# Audio.net
KiCad netlist of a schematic drawn in Altium Designer
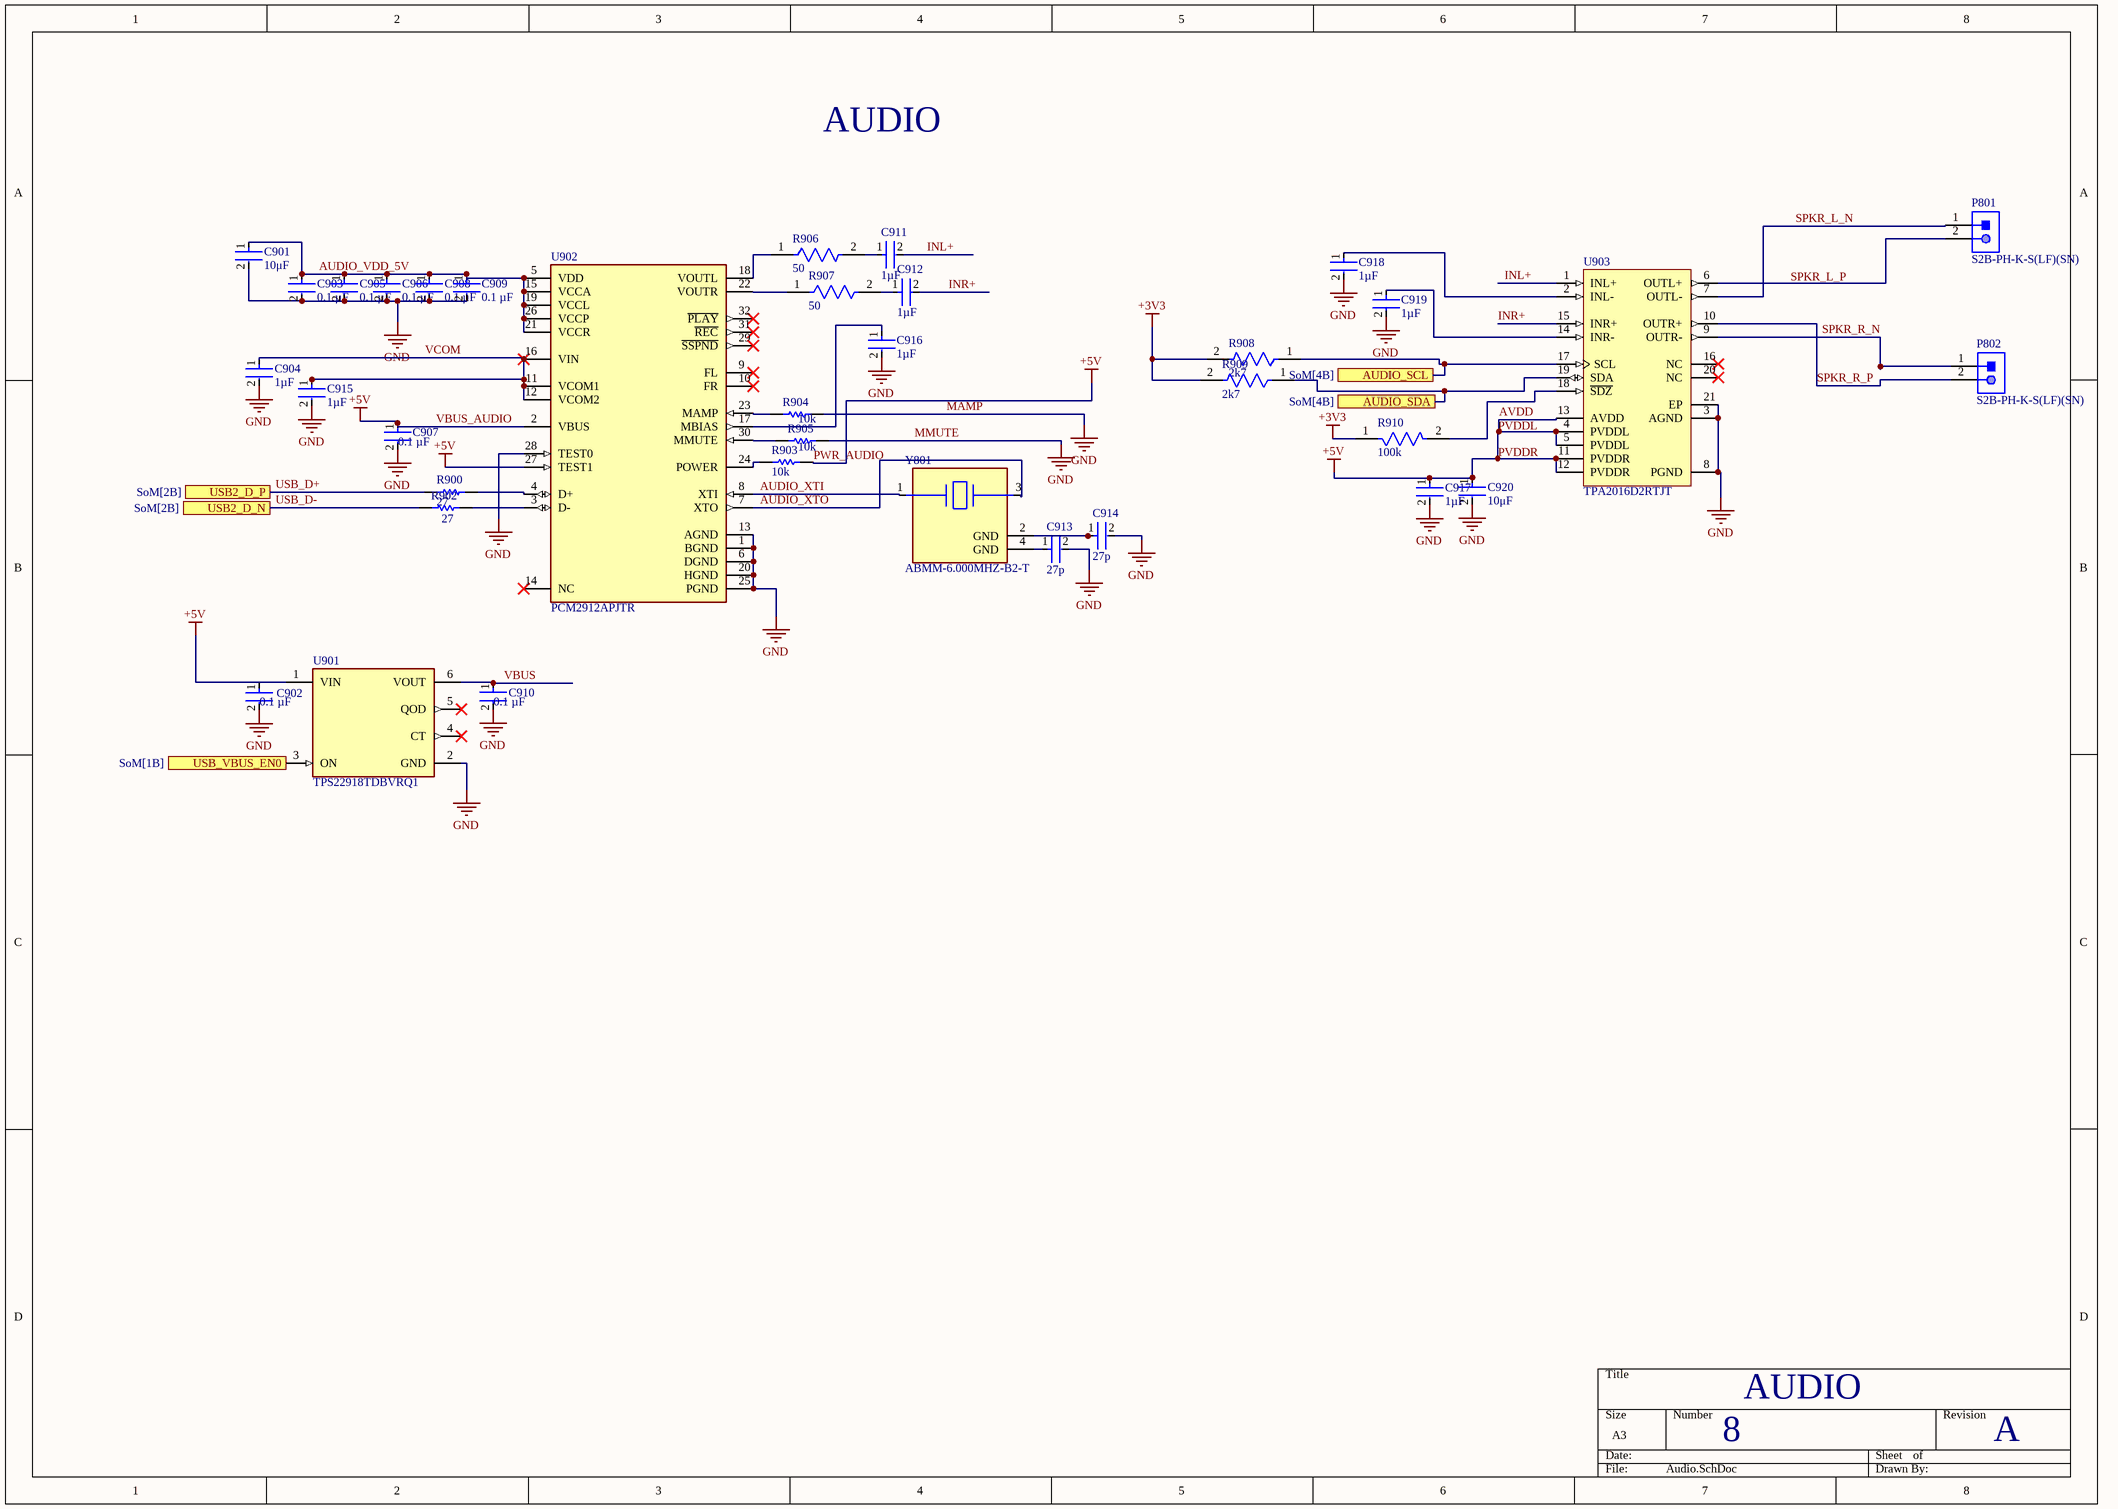
[diagram p0: Audio.SchDoc]

(export (version "E")
  (design (tool "Eeschema 10.0.6"))
  (components
    (comp (ref "C901")
      (value "10μF")
      (footprint "FP-GRM31C-0_2-e0_3_0_8-MFG")
      (description "Chip Multilayer Ceramic Capacitors for General Purpose, 1206, 10uF, X7R, 15%, 10%, 25V")
      (fields (field (name "TOLERANCE") "10%") (field (name "VOLTAGE") "25V"))
      (libsource (lib "Altium Content Vault") (part "02cd4be3c70576c341d710602a673aa"))
    )
    (comp (ref "C902")
      (value "0.1 µF")
      (footprint "FP-GRM155-0_05-IPC_B")
      (description "Chip Multilayer Ceramic Capacitors for General Purpose, 0402, 0.10uF, X7R, 15%, 10%, 50V")
      (fields (field (name "TOLERANCE") "10%"))
      (libsource (lib "Altium Content Vault") (part "02cd4be3c70576c341d710602a673aa"))
    )
    (comp (ref "C903")
      (value "0.1 µF")
      (footprint "FP-GRM155-0_05-IPC_B")
      (description "Chip Multilayer Ceramic Capacitors for General Purpose, 0402, 0.10uF, X7R, 15%, 10%, 50V")
      (fields (field (name "TOLERANCE") "10%"))
      (libsource (lib "Altium Content Vault") (part "02cd4be3c70576c341d710602a673aa"))
    )
    (comp (ref "C904")
      (value "1µF")
      (footprint "FP-GRM15-0_1-MFG")
      (description "CAP CER 1UF 10V X5R 0402")
      (fields
        (field (name "OCTOPART") "https://octopart.com/grm155r61a105ke15d-murata-197442")
        (field (name "MANUFACTURER PART NUMBER") "GRM155R61A105KE15D")
      )
      (libsource (lib "Altium Content Vault") (part "02cd4be3c70576c341d710602a673aa"))
    )
    (comp (ref "C905")
      (value "0.1 µF")
      (footprint "FP-GRM155-0_05-IPC_B")
      (description "Chip Multilayer Ceramic Capacitors for General Purpose, 0402, 0.10uF, X7R, 15%, 10%, 50V")
      (fields (field (name "TOLERANCE") "10%"))
      (libsource (lib "Altium Content Vault") (part "02cd4be3c70576c341d710602a673aa"))
    )
    (comp (ref "C906")
      (value "0.1 µF")
      (footprint "FP-GRM155-0_05-IPC_B")
      (description "Chip Multilayer Ceramic Capacitors for General Purpose, 0402, 0.10uF, X7R, 15%, 10%, 50V")
      (fields (field (name "TOLERANCE") "10%"))
      (libsource (lib "Altium Content Vault") (part "02cd4be3c70576c341d710602a673aa"))
    )
    (comp (ref "C907")
      (value "0.1 µF")
      (footprint "FP-GRM155-0_05-IPC_B")
      (description "Chip Multilayer Ceramic Capacitors for General Purpose, 0402, 0.10uF, X7R, 15%, 10%, 50V")
      (fields (field (name "TOLERANCE") "10%"))
      (libsource (lib "Altium Content Vault") (part "02cd4be3c70576c341d710602a673aa"))
    )
    (comp (ref "C908")
      (value "0.1 µF")
      (footprint "FP-GRM155-0_05-IPC_B")
      (description "Chip Multilayer Ceramic Capacitors for General Purpose, 0402, 0.10uF, X7R, 15%, 10%, 50V")
      (fields (field (name "TOLERANCE") "10%"))
      (libsource (lib "Altium Content Vault") (part "02cd4be3c70576c341d710602a673aa"))
    )
    (comp (ref "C909")
      (value "0.1 µF")
      (footprint "FP-GRM155-0_05-IPC_B")
      (description "Chip Multilayer Ceramic Capacitors for General Purpose, 0402, 0.10uF, X7R, 15%, 10%, 50V")
      (fields (field (name "TOLERANCE") "10%"))
      (libsource (lib "Altium Content Vault") (part "02cd4be3c70576c341d710602a673aa"))
    )
    (comp (ref "C910")
      (value "0.1 µF")
      (footprint "FP-GRM155-0_05-IPC_B")
      (description "Chip Multilayer Ceramic Capacitors for General Purpose, 0402, 0.10uF, X7R, 15%, 10%, 50V")
      (fields (field (name "TOLERANCE") "10%"))
      (libsource (lib "Altium Content Vault") (part "02cd4be3c70576c341d710602a673aa"))
    )
    (comp (ref "C911")
      (value "1µF")
      (footprint "FP-GRM15-0_1-MFG")
      (description "CAP CER 1UF 10V X5R 0402")
      (fields
        (field (name "OCTOPART") "https://octopart.com/grm155r61a105ke15d-murata-197442")
        (field (name "MANUFACTURER PART NUMBER") "GRM155R61A105KE15D")
      )
      (libsource (lib "Altium Content Vault") (part "02cd4be3c70576c341d710602a673aa"))
    )
    (comp (ref "C912")
      (value "1µF")
      (footprint "FP-GRM15-0_1-MFG")
      (description "CAP CER 1UF 10V X5R 0402")
      (fields
        (field (name "OCTOPART") "https://octopart.com/grm155r61a105ke15d-murata-197442")
        (field (name "MANUFACTURER PART NUMBER") "GRM155R61A105KE15D")
      )
      (libsource (lib "Altium Content Vault") (part "02cd4be3c70576c341d710602a673aa"))
    )
    (comp (ref "C913")
      (value "27p")
      (footprint "FP-C0603C-CF-MFG")
      (description "C0603 27 pF X7R 30ppm/°C 5.00% 50 V")
      (fields
        (field (name "OCTOPART") "https://octopart.com/c0603c270j5ractu-kemet-82267354")
        (field (name "TOLERANCE") "0.05")
      )
      (libsource (lib "Altium Content Vault") (part "b4654b650e69147ec39a6b967a45e02"))
    )
    (comp (ref "C914")
      (value "27p")
      (footprint "FP-C0603C-CF-MFG")
      (description "C0603 27 pF X7R 30ppm/°C 5.00% 50 V")
      (fields
        (field (name "OCTOPART") "https://octopart.com/c0603c270j5ractu-kemet-82267354")
        (field (name "TOLERANCE") "0.05")
      )
      (libsource (lib "Altium Content Vault") (part "b4654b650e69147ec39a6b967a45e02"))
    )
    (comp (ref "C915")
      (value "1µF")
      (footprint "FP-GRM15-0_1-MFG")
      (description "CAP CER 1UF 10V X5R 0402")
      (fields
        (field (name "OCTOPART") "https://octopart.com/grm155r61a105ke15d-murata-197442")
        (field (name "MANUFACTURER PART NUMBER") "GRM155R61A105KE15D")
      )
      (libsource (lib "Altium Content Vault") (part "02cd4be3c70576c341d710602a673aa"))
    )
    (comp (ref "C916")
      (value "1µF")
      (footprint "FP-GRM15-0_1-MFG")
      (description "CAP CER 1UF 10V X5R 0402")
      (fields
        (field (name "OCTOPART") "https://octopart.com/grm155r61a105ke15d-murata-197442")
        (field (name "MANUFACTURER PART NUMBER") "GRM155R61A105KE15D")
      )
      (libsource (lib "Altium Content Vault") (part "02cd4be3c70576c341d710602a673aa"))
    )
    (comp (ref "C917")
      (value "1µF")
      (footprint "FP-GRM15-0_1-MFG")
      (description "CAP CER 1UF 10V X5R 0402")
      (fields
        (field (name "OCTOPART") "https://octopart.com/grm155r61a105ke15d-murata-197442")
        (field (name "MANUFACTURER PART NUMBER") "GRM155R61A105KE15D")
      )
      (libsource (lib "Altium Content Vault") (part "02cd4be3c70576c341d710602a673aa"))
    )
    (comp (ref "C918")
      (value "1µF")
      (footprint "FP-GRM15-0_1-MFG")
      (description "CAP CER 1UF 10V X5R 0402")
      (fields
        (field (name "OCTOPART") "https://octopart.com/grm155r61a105ke15d-murata-197442")
        (field (name "MANUFACTURER PART NUMBER") "GRM155R61A105KE15D")
      )
      (libsource (lib "Altium Content Vault") (part "02cd4be3c70576c341d710602a673aa"))
    )
    (comp (ref "C919")
      (value "1µF")
      (footprint "FP-GRM15-0_1-MFG")
      (description "CAP CER 1UF 10V X5R 0402")
      (fields
        (field (name "OCTOPART") "https://octopart.com/grm155r61a105ke15d-murata-197442")
        (field (name "MANUFACTURER PART NUMBER") "GRM155R61A105KE15D")
      )
      (libsource (lib "Altium Content Vault") (part "02cd4be3c70576c341d710602a673aa"))
    )
    (comp (ref "C920")
      (value "10μF")
      (footprint "FP-GRM31C-0_2-e0_3_0_8-MFG")
      (description "Chip Multilayer Ceramic Capacitors for General Purpose, 1206, 10uF, X7R, 15%, 10%, 25V")
      (fields (field (name "TOLERANCE") "10%") (field (name "VOLTAGE") "25V"))
      (libsource (lib "Altium Content Vault") (part "02cd4be3c70576c341d710602a673aa"))
    )
    (comp (ref "P801")
      (value "S2B-PH-K-S(LF)(SN)")
      (footprint "JST-S2B-PH-K-S_V")
      (fields (field (name "TOLERANCE") "20%"))
      (libsource (lib "Altium Content Vault") (part "CN-1P-M-R2"))
    )
    (comp (ref "P802")
      (value "S2B-PH-K-S(LF)(SN)")
      (footprint "JST-S2B-PH-K-S_V")
      (fields (field (name "TOLERANCE") "20%"))
      (libsource (lib "Altium Content Vault") (part "CN-1P-M-R2"))
    )
    (comp (ref "R900")
      (value "27")
      (footprint "RESC1005X40X25LL05T10")
      (fields (field (name "PART NUMBER") "RC0402FR-0727RL") (field (name "MANUFACTURER") "Yageo / Phycomp"))
      (libsource (lib "Altium Content Vault") (part "RES"))
    )
    (comp (ref "R902")
      (value "27")
      (footprint "RESC1005X40X25LL05T10")
      (fields (field (name "PART NUMBER") "RC0402FR-0727RL") (field (name "MANUFACTURER") "Yageo / Phycomp"))
      (libsource (lib "Altium Content Vault") (part "RES"))
    )
    (comp (ref "R903")
      (value "10k")
      (footprint "RESC1005X40X25LL05T10")
      (fields (field (name "PART NUMBER") "RC0402FR-0710KL") (field (name "MANUFACTURER") "Yageo / Phycomp"))
      (libsource (lib "Altium Content Vault") (part "RES"))
    )
    (comp (ref "R904")
      (value "10k")
      (footprint "RESC1005X40X25LL05T10")
      (fields (field (name "PART NUMBER") "RC0402FR-0710KL") (field (name "MANUFACTURER") "Yageo / Phycomp"))
      (libsource (lib "Altium Content Vault") (part "RES"))
    )
    (comp (ref "R905")
      (value "10k")
      (footprint "RESC1005X40X25LL05T10")
      (fields (field (name "PART NUMBER") "RC0402FR-0710KL") (field (name "MANUFACTURER") "Yageo / Phycomp"))
      (libsource (lib "Altium Content Vault") (part "RES"))
    )
    (comp (ref "R906")
      (value "50")
      (footprint "FP-CRCW0603-e3-MFG")
      (description "RES Thick Film, 50Ω, 1%, 0.1W, 100ppm/°C, 0603")
      (fields (field (name "TOLERANCE") "1%"))
      (libsource (lib "Altium Content Vault") (part "1029c3af85768c4190bb7ad29bc67b5"))
    )
    (comp (ref "R907")
      (value "50")
      (footprint "FP-CRCW0603-e3-MFG")
      (description "RES Thick Film, 50Ω, 1%, 0.1W, 100ppm/°C, 0603")
      (fields (field (name "TOLERANCE") "1%"))
      (libsource (lib "Altium Content Vault") (part "1029c3af85768c4190bb7ad29bc67b5"))
    )
    (comp (ref "R908")
      (value "2k7")
      (footprint "FP-CR0402-IPC_B")
      (description "Thick Film Chip Resistors 0402 2.7kΩ 0.0625W 1% 100ppm/°C")
      (fields (field (name "TOLERANCE") "1%"))
      (libsource (lib "Altium Content Vault") (part "1029c3af85768c4190bb7ad29bc67b5"))
    )
    (comp (ref "R909")
      (value "2k7")
      (footprint "FP-CR0402-IPC_B")
      (description "Thick Film Chip Resistors 0402 2.7kΩ 0.0625W 1% 100ppm/°C")
      (fields (field (name "TOLERANCE") "1%"))
      (libsource (lib "Altium Content Vault") (part "1029c3af85768c4190bb7ad29bc67b5"))
    )
    (comp (ref "R910")
      (value "100k")
      (footprint "FP-RC0402-0_4-IPC_A")
      (description "RES 100K OHM 5% 1/16W 0402")
      (fields (field (name "TOLERANCE") "5%"))
      (libsource (lib "Altium Content Vault") (part "1029c3af85768c4190bb7ad29bc67b5"))
    )
    (comp (ref "U901")
      (value "TPS22918TDBVRQ1")
      (footprint "FP-DBV0006A-IPC_C")
      (description "IC PWR SWITCH N-CHAN 1:1 SOT23-6")
      (libsource (lib "Altium Content Vault") (part "8b1f3cf37ce29d5f7477cf0fde67f53"))
    )
    (comp (ref "U902")
      (value "PCM2912APJTR")
      (footprint "FP-PJT0032A-IPC_C")
      (description "IC STEREO AUD CODEC W/USB 32TQFP")
      (libsource (lib "Altium Content Vault") (part "253ddf6499021ded57be087bdc4fbd2"))
    )
    (comp (ref "U903")
      (value "TPA2016D2RTJT")
      (footprint "RTJ0020D_V")
      (fields (field (name "MANUFACTURER") "Texas Instruments"))
      (libsource (lib "Altium Content Vault") (part "TI-TPA2016D2RTJ20-2700X2700TP"))
    )
    (comp (ref "Y801")
      (value "ABMM-6.000MHZ-B2-T")
      (footprint "FP-ABMM-MFG")
      (description "CRYSTAL 6.0000MHZ 18PF SMD")
      (fields (field (name "TOLERANCE") "20ppm"))
      (libsource (lib "Altium Content Vault") (part "14e648fd3e94df574add110f4c202a0"))
    )
  )
  (nets
    (net (code "1") (name "+3V3") (class "Default")
      (node (ref "R908") (pin "2") (pinfunction "2_2") (pintype "passive"))
      (node (ref "R909") (pin "2") (pinfunction "2_2") (pintype "passive"))
      (node (ref "R910") (pin "1") (pinfunction "1_1") (pintype "passive"))
    )
    (net (code "2") (name "+5V") (class "Default")
      (node (ref "C917") (pin "1") (pinfunction "1_1") (pintype "passive"))
      (node (ref "C920") (pin "1") (pinfunction "1_1") (pintype "passive"))
      (node (ref "R903") (pin "1") (pinfunction "1_1") (pintype "passive"))
      (node (ref "U901") (pin "1") (pinfunction "VIN_1") (pintype "power_in"))
      (node (ref "U902") (pin "27") (pinfunction "TEST1_27") (pintype "input"))
      (node (ref "U903") (pin "11") (pinfunction "PVDDR_11") (pintype "power_in"))
      (node (ref "U903") (pin "12") (pinfunction "PVDDR_12") (pintype "power_in"))
      (node (ref "U903") (pin "13") (pinfunction "AVDD_13") (pintype "power_in"))
      (node (ref "U903") (pin "4") (pinfunction "PVDDL_4") (pintype "power_in"))
      (node (ref "U903") (pin "5") (pinfunction "PVDDL_5") (pintype "power_in"))
    )
    (net (code "3") (name "/AUDIO_SCL") (class "Default")
      (node (ref "R908") (pin "1") (pinfunction "1_1") (pintype "passive"))
      (node (ref "U903") (pin "17") (pinfunction "SCL_17") (pintype "input"))
    )
    (net (code "4") (name "/AUDIO_SDA") (class "Default")
      (node (ref "R909") (pin "1") (pinfunction "1_1") (pintype "passive"))
      (node (ref "U903") (pin "19") (pinfunction "SDA_19") (pintype "bidirectional"))
    )
    (net (code "5") (name "/AUDIO_VDD_5V") (class "Default")
      (node (ref "C901") (pin "1") (pinfunction "1_1") (pintype "passive"))
      (node (ref "C903") (pin "1") (pinfunction "1_1") (pintype "passive"))
      (node (ref "C905") (pin "1") (pinfunction "1_1") (pintype "passive"))
      (node (ref "C906") (pin "1") (pinfunction "1_1") (pintype "passive"))
      (node (ref "C908") (pin "1") (pinfunction "1_1") (pintype "passive"))
      (node (ref "C909") (pin "1") (pinfunction "1_1") (pintype "passive"))
      (node (ref "U902") (pin "15") (pinfunction "VCCA_15") (pintype "power_in"))
      (node (ref "U902") (pin "19") (pinfunction "VCCL_19") (pintype "power_in"))
      (node (ref "U902") (pin "21") (pinfunction "VCCR_21") (pintype "power_in"))
      (node (ref "U902") (pin "26") (pinfunction "VCCP_26") (pintype "power_in"))
      (node (ref "U902") (pin "5") (pinfunction "VDD_5") (pintype "power_in"))
    )
    (net (code "6") (name "/AUDIO_XTI") (class "Default")
      (node (ref "U902") (pin "8") (pinfunction "XTI_8") (pintype "input"))
      (node (ref "Y801") (pin "1") (pinfunction "1_1") (pintype "passive"))
    )
    (net (code "7") (name "/AUDIO_XTO") (class "Default")
      (node (ref "U902") (pin "7") (pinfunction "XTO_7") (pintype "output"))
      (node (ref "Y801") (pin "3") (pinfunction "3_3") (pintype "passive"))
    )
    (net (code "8") (name "/INL+") (class "Default")
      (node (ref "C911") (pin "2") (pinfunction "2_2") (pintype "passive"))
      (node (ref "U903") (pin "1") (pinfunction "INL+_1") (pintype "input"))
    )
    (net (code "9") (name "/INR+") (class "Default")
      (node (ref "C912") (pin "2") (pinfunction "2_2") (pintype "passive"))
      (node (ref "U903") (pin "15") (pinfunction "INR+_15") (pintype "input"))
    )
    (net (code "10") (name "/SPKR_L_N") (class "Default")
      (node (ref "P801") (pin "1") (pinfunction "1_1") (pintype "passive"))
      (node (ref "U903") (pin "7") (pinfunction "OUTL-_7") (pintype "output"))
    )
    (net (code "12") (name "/SPKR_R_N") (class "Default")
      (node (ref "P802") (pin "1") (pinfunction "1_1") (pintype "passive"))
      (node (ref "U903") (pin "9") (pinfunction "OUTR-_9") (pintype "output"))
    )
    (net (code "13") (name "/SPKR_R_P") (class "Default")
      (node (ref "P802") (pin "2") (pinfunction "2_2") (pintype "passive"))
      (node (ref "U903") (pin "10") (pinfunction "OUTR+_10") (pintype "output"))
    )
    (net (code "15") (name "/USB_D+") (class "Default")
      (node (ref "R900") (pin "1") (pinfunction "1_1") (pintype "passive"))
    )
    (net (code "16") (name "/USB_D-") (class "Default")
      (node (ref "R902") (pin "1") (pinfunction "1_1") (pintype "passive"))
    )
    (net (code "17") (name "/USB_VBUS_EN0") (class "Default")
      (node (ref "U901") (pin "3") (pinfunction "ON_3") (pintype "input"))
    )
    (net (code "18") (name "/VBUS") (class "Default")
      (node (ref "C910") (pin "1") (pinfunction "1_1") (pintype "passive"))
      (node (ref "U901") (pin "6") (pinfunction "VOUT_6") (pintype "power_in"))
    )
    (net (code "19") (name "/VBUS_AUDIO") (class "Default")
      (node (ref "C907") (pin "1") (pinfunction "1_1") (pintype "passive"))
      (node (ref "U902") (pin "2") (pinfunction "VBUS_2") (pintype "power_in"))
    )
    (net (code "20") (name "/VCOM") (class "Default")
      (node (ref "C904") (pin "1") (pinfunction "1_1") (pintype "passive"))
      (node (ref "C915") (pin "1") (pinfunction "1_1") (pintype "passive"))
      (node (ref "U902") (pin "11") (pinfunction "VCOM1_11") (pintype "power_in"))
      (node (ref "U902") (pin "12") (pinfunction "VCOM2_12") (pintype "power_in"))
      (node (ref "U902") (pin "16") (pinfunction "VIN_16") (pintype "power_in"))
    )
    (net (code "21") (name "GND") (class "Default")
      (node (ref "C901") (pin "2") (pinfunction "2_2") (pintype "passive"))
      (node (ref "C902") (pin "2") (pinfunction "2_2") (pintype "passive"))
      (node (ref "C903") (pin "2") (pinfunction "2_2") (pintype "passive"))
      (node (ref "C904") (pin "2") (pinfunction "2_2") (pintype "passive"))
      (node (ref "C905") (pin "2") (pinfunction "2_2") (pintype "passive"))
      (node (ref "C906") (pin "2") (pinfunction "2_2") (pintype "passive"))
      (node (ref "C907") (pin "2") (pinfunction "2_2") (pintype "passive"))
      (node (ref "C908") (pin "2") (pinfunction "2_2") (pintype "passive"))
      (node (ref "C909") (pin "2") (pinfunction "2_2") (pintype "passive"))
      (node (ref "C910") (pin "2") (pinfunction "2_2") (pintype "passive"))
      (node (ref "C913") (pin "2") (pinfunction "2_2") (pintype "passive"))
      (node (ref "C914") (pin "2") (pinfunction "2_2") (pintype "passive"))
      (node (ref "C915") (pin "2") (pinfunction "2_2") (pintype "passive"))
      (node (ref "C916") (pin "2") (pinfunction "2_2") (pintype "passive"))
      (node (ref "C917") (pin "2") (pinfunction "2_2") (pintype "passive"))
      (node (ref "C918") (pin "2") (pinfunction "2_2") (pintype "passive"))
      (node (ref "C919") (pin "2") (pinfunction "2_2") (pintype "passive"))
      (node (ref "C920") (pin "2") (pinfunction "2_2") (pintype "passive"))
      (node (ref "R904") (pin "1") (pinfunction "1_1") (pintype "passive"))
      (node (ref "R905") (pin "1") (pinfunction "1_1") (pintype "passive"))
      (node (ref "U901") (pin "2") (pinfunction "GND_2") (pintype "power_in"))
      (node (ref "U902") (pin "1") (pinfunction "BGND_1") (pintype "power_in"))
      (node (ref "U902") (pin "13") (pinfunction "AGND_13") (pintype "power_in"))
      (node (ref "U902") (pin "20") (pinfunction "HGND_20") (pintype "power_in"))
      (node (ref "U902") (pin "25") (pinfunction "PGND_25") (pintype "power_in"))
      (node (ref "U902") (pin "28") (pinfunction "TEST0_28") (pintype "input"))
      (node (ref "U902") (pin "6") (pinfunction "DGND_6") (pintype "power_in"))
      (node (ref "U903") (pin "21") (pinfunction "EP_21") (pintype "passive"))
      (node (ref "U903") (pin "3") (pinfunction "AGND_3") (pintype "power_in"))
      (node (ref "U903") (pin "8") (pinfunction "PGND_8") (pintype "power_in"))
    )
    (net (code "22") (name "Net-(C911-Pad1)") (class "Default")
      (node (ref "C911") (pin "1") (pinfunction "1_1") (pintype "passive"))
      (node (ref "R906") (pin "2") (pinfunction "2_2") (pintype "passive"))
    )
    (net (code "23") (name "Net-(C912-Pad1)") (class "Default")
      (node (ref "C912") (pin "1") (pinfunction "1_1") (pintype "passive"))
      (node (ref "R907") (pin "2") (pinfunction "2_2") (pintype "passive"))
    )
    (net (code "24") (name "Net-(C913-Pad1)") (class "Default")
      (node (ref "C913") (pin "1") (pinfunction "1_1") (pintype "passive"))
      (node (ref "Y801") (pin "4") (pinfunction "GND_4") (pintype "passive"))
    )
    (net (code "25") (name "Net-(C914-Pad1)") (class "Default")
      (node (ref "C914") (pin "1") (pinfunction "1_1") (pintype "passive"))
      (node (ref "Y801") (pin "2") (pinfunction "GND_2") (pintype "passive"))
    )
    (net (code "26") (name "Net-(U902-D+)") (class "Default")
      (node (ref "R900") (pin "2") (pinfunction "2_2") (pintype "passive"))
      (node (ref "U902") (pin "4") (pinfunction "D+_4") (pintype "bidirectional"))
    )
    (net (code "27") (name "Net-(U902-D-)") (class "Default")
      (node (ref "R902") (pin "2") (pinfunction "2_2") (pintype "passive"))
      (node (ref "U902") (pin "3") (pinfunction "D-_3") (pintype "bidirectional"))
    )
    (net (code "28") (name "Net-(U902-MAMP)") (class "Default")
      (node (ref "R904") (pin "2") (pinfunction "2_2") (pintype "passive"))
      (node (ref "U902") (pin "23") (pinfunction "MAMP_23") (pintype "input"))
    )
    (net (code "29") (name "Net-(U902-MBIAS)") (class "Default")
      (node (ref "C916") (pin "1") (pinfunction "1_1") (pintype "passive"))
      (node (ref "U902") (pin "17") (pinfunction "MBIAS_17") (pintype "output"))
    )
    (net (code "30") (name "Net-(U902-MMUTE)") (class "Default")
      (node (ref "R905") (pin "2") (pinfunction "2_2") (pintype "passive"))
      (node (ref "U902") (pin "30") (pinfunction "MMUTE_30") (pintype "input"))
    )
    (net (code "31") (name "Net-(U902-POWER)") (class "Default")
      (node (ref "R903") (pin "2") (pinfunction "2_2") (pintype "passive"))
      (node (ref "U902") (pin "24") (pinfunction "POWER_24") (pintype "power_in"))
    )
    (net (code "32") (name "Net-(U902-VOUTL)") (class "Default")
      (node (ref "R906") (pin "1") (pinfunction "1_1") (pintype "passive"))
      (node (ref "U902") (pin "18") (pinfunction "VOUTL_18") (pintype "power_in"))
    )
    (net (code "33") (name "Net-(U902-VOUTR)") (class "Default")
      (node (ref "R907") (pin "1") (pinfunction "1_1") (pintype "passive"))
      (node (ref "U902") (pin "22") (pinfunction "VOUTR_22") (pintype "power_in"))
    )
    (net (code "34") (name "Net-(U903-INL-)") (class "Default")
      (node (ref "C918") (pin "1") (pinfunction "1_1") (pintype "passive"))
      (node (ref "U903") (pin "2") (pinfunction "INL-_2") (pintype "input"))
    )
    (net (code "35") (name "Net-(U903-INR-)") (class "Default")
      (node (ref "C919") (pin "1") (pinfunction "1_1") (pintype "passive"))
      (node (ref "U903") (pin "14") (pinfunction "INR-_14") (pintype "input"))
    )
    (net (code "36") (name "Net-(U903-OUTL+)") (class "Default")
      (node (ref "P801") (pin "2") (pinfunction "2_2") (pintype "passive"))
      (node (ref "U903") (pin "6") (pinfunction "OUTL+_6") (pintype "output"))
    )
    (net (code "37") (name "Net-(U903-~{SDZ})") (class "Default")
      (node (ref "R910") (pin "2") (pinfunction "2_2") (pintype "passive"))
      (node (ref "U903") (pin "18") (pinfunction "~{SDZ}_18") (pintype "input"))
    )
    (net (code "38") (name "unconnected-(C902-Pad1)") (class "Default")
      (node (ref "C902") (pin "1") (pinfunction "1_1") (pintype "passive"))
    )
    (net (code "39") (name "unconnected-(U901-CT-Pad4)") (class "Default")
      (node (ref "U901") (pin "4") (pinfunction "CT_4") (pintype "output+no_connect"))
    )
    (net (code "40") (name "unconnected-(U901-QOD-Pad5)") (class "Default")
      (node (ref "U901") (pin "5") (pinfunction "QOD_5") (pintype "output+no_connect"))
    )
    (net (code "41") (name "unconnected-(U902-FL-Pad9)") (class "Default")
      (node (ref "U902") (pin "9") (pinfunction "FL_9") (pintype "passive+no_connect"))
    )
    (net (code "42") (name "unconnected-(U902-FR-Pad10)") (class "Default")
      (node (ref "U902") (pin "10") (pinfunction "FR_10") (pintype "passive+no_connect"))
    )
    (net (code "43") (name "unconnected-(U902-NC-Pad14)") (class "Default")
      (node (ref "U902") (pin "14") (pinfunction "NC_14") (pintype "passive+no_connect"))
    )
    (net (code "44") (name "unconnected-(U902-~{PLAY}-Pad32)") (class "Default")
      (node (ref "U902") (pin "32") (pinfunction "~{PLAY}_32") (pintype "output+no_connect"))
    )
    (net (code "45") (name "unconnected-(U902-~{REC}-Pad31)") (class "Default")
      (node (ref "U902") (pin "31") (pinfunction "~{REC}_31") (pintype "output+no_connect"))
    )
    (net (code "46") (name "unconnected-(U902-~{SSPND}-Pad29)") (class "Default")
      (node (ref "U902") (pin "29") (pinfunction "~{SSPND}_29") (pintype "output+no_connect"))
    )
    (net (code "47") (name "unconnected-(U903-NC-Pad16)") (class "Default")
      (node (ref "U903") (pin "16") (pinfunction "NC_16") (pintype "passive+no_connect"))
    )
    (net (code "48") (name "unconnected-(U903-NC-Pad20)") (class "Default")
      (node (ref "U903") (pin "20") (pinfunction "NC_20") (pintype "passive+no_connect"))
    )
  )
)
